# Power_Controller_V1_0.net
KiCad netlist of a schematic drawn in Altium Designer
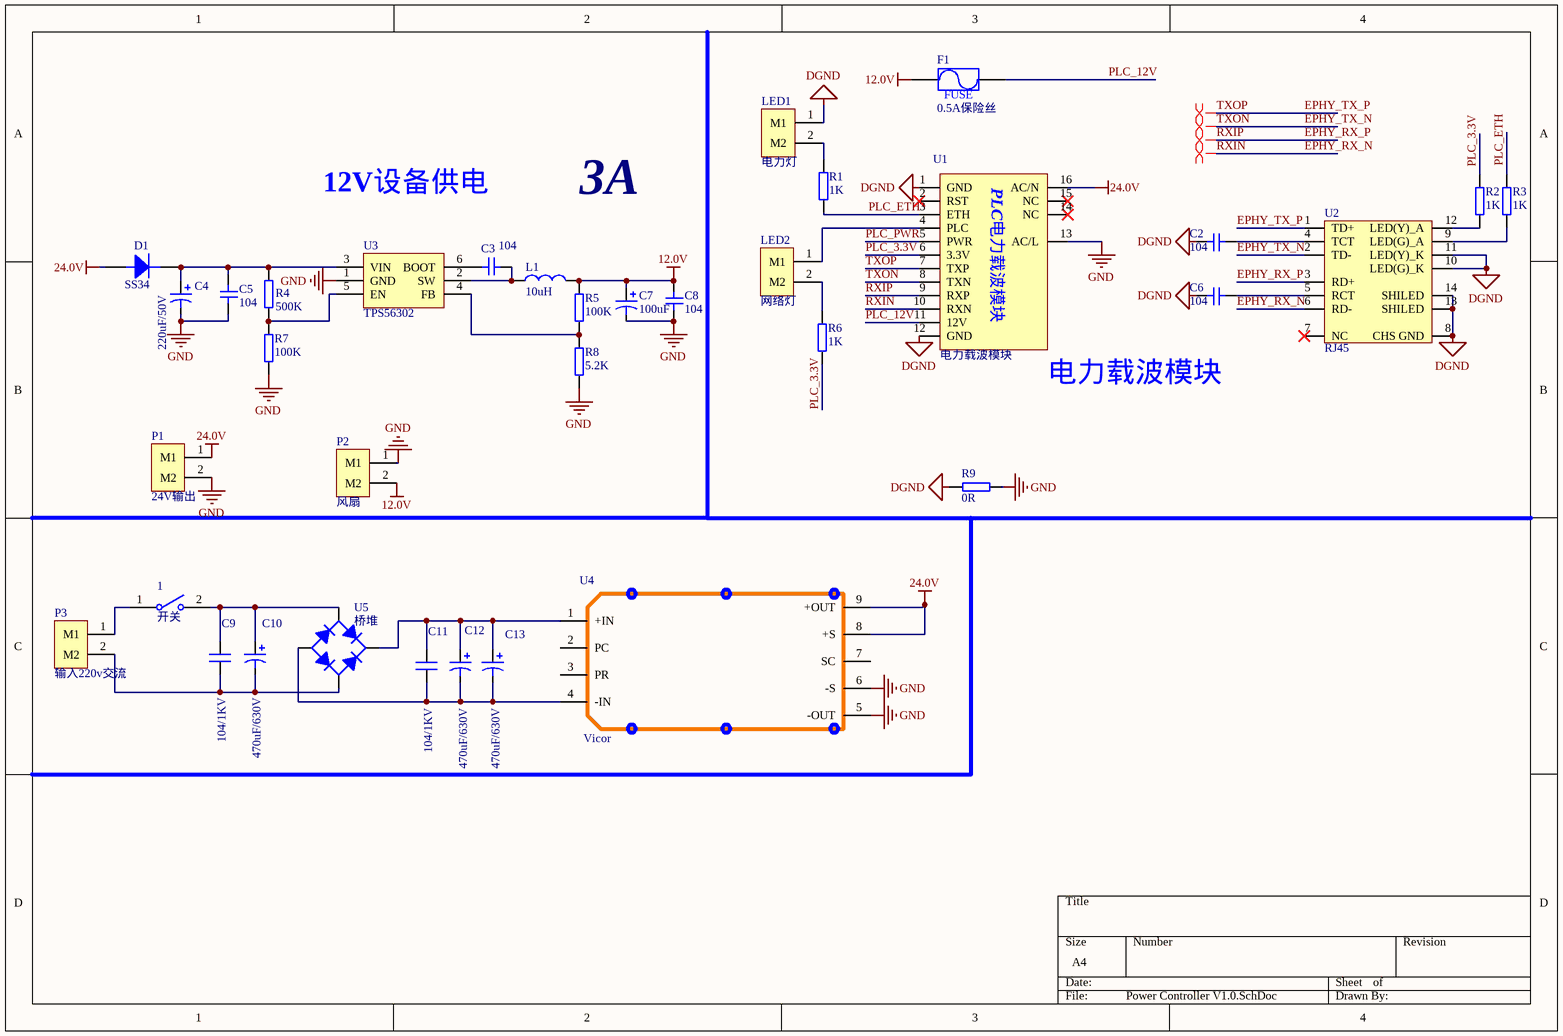
[diagram p0: Power Controller V1.0.SchDoc]

(export (version "E")
  (design (tool "Eeschema 10.0.6"))
  (components
    (comp (ref "1") (value "开关") (footprint "XT60-F") (libsource (lib "Schlib2") (part "开关")))
    (comp (ref "C2")
      (value "104")
      (footprint "0805C")
      (description "无极贴片电容")
      (libsource (lib "集大电协1.1.2") (part "Cap1"))
    )
    (comp (ref "C3")
      (value "104")
      (footprint "0805C")
      (description "无极贴片电容")
      (libsource (lib "集大电协1.5") (part "Cap1"))
    )
    (comp (ref "C4")
      (value "220uF/50V")
      (footprint "RB.1.2")
      (description "直插极性电容")
      (libsource (lib "集大电协1.5") (part "Cap3"))
    )
    (comp (ref "C5")
      (value "104")
      (footprint "0805C")
      (description "无极贴片电容")
      (libsource (lib "集大电协1.5") (part "Cap1"))
    )
    (comp (ref "C6")
      (value "104")
      (footprint "0805C")
      (description "无极贴片电容")
      (libsource (lib "集大电协1.1.2") (part "Cap1"))
    )
    (comp (ref "C7")
      (value "100uF")
      (footprint "TAJ-C")
      (description "极性贴片电容")
      (libsource (lib "集大电协1.5") (part "Pol Cap"))
    )
    (comp (ref "C8")
      (value "104")
      (footprint "0805C")
      (description "无极贴片电容")
      (libsource (lib "集大电协1.5") (part "Cap1"))
    )
    (comp (ref "C9")
      (value "104/1KV")
      (footprint "无极性直插电容")
      (description "无极直插电容")
      (libsource (lib "集大电协1.5(1)") (part "Cap2"))
    )
    (comp (ref "C10")
      (value "470uF/630V")
      (footprint "RB.2.4")
      (description "直插极性电容")
      (libsource (lib "集大电协1.5(1)") (part "Cap3"))
    )
    (comp (ref "C11")
      (value "104/1KV")
      (footprint "无极性直插电容")
      (description "无极直插电容")
      (libsource (lib "集大电协1.5(1)") (part "Cap2"))
    )
    (comp (ref "C12")
      (value "470uF/630V")
      (footprint "RB.2.4")
      (description "直插极性电容")
      (libsource (lib "集大电协1.5(1)") (part "Cap3"))
    )
    (comp (ref "C13")
      (value "470uF/630V")
      (footprint "RB.2.4")
      (description "直插极性电容")
      (libsource (lib "集大电协1.5(1)") (part "Cap3"))
    )
    (comp (ref "D1")
      (value "SS34")
      (footprint "SMA/DO-214AC")
      (description "二极管")
      (libsource (lib "集大电协1.5") (part "Diode"))
    )
    (comp (ref "F1")
      (value "0.5A保险丝")
      (footprint "FUSE-1206")
      (description "保险丝")
      (libsource (lib "集大电协1.2") (part "Fuse"))
    )
    (comp (ref "L1")
      (value "10uH")
      (footprint "CDRH124")
      (description "电感")
      (libsource (lib "集大电协1.5") (part "L"))
    )
    (comp (ref "LED1")
      (value "电力灯")
      (footprint "XH2/2.54mm/180")
      (description "2PIN")
      (libsource (lib "集大电协1.5") (part "接线端子-2PIN"))
    )
    (comp (ref "LED2")
      (value "网络灯")
      (footprint "XH2/2.54mm/180")
      (description "2PIN")
      (libsource (lib "集大电协1.5") (part "接线端子-2PIN"))
    )
    (comp (ref "P1")
      (value "24V输出")
      (footprint "XT60-F")
      (description "2PIN")
      (libsource (lib "集大电协1.5(1)") (part "接线端子-2PIN"))
    )
    (comp (ref "P2")
      (value "风扇")
      (footprint "接线端子(2.54mm)-2PIN")
      (description "2PIN")
      (libsource (lib "集大电协1.5(1)") (part "接线端子-2PIN"))
    )
    (comp (ref "P3")
      (value "输入220v交流")
      (footprint "XT60-F")
      (description "2PIN")
      (libsource (lib "集大电协1.5(1)") (part "接线端子-2PIN"))
    )
    (comp (ref "R1")
      (value "1K")
      (footprint "0805R")
      (description "电阻")
      (libsource (lib "集大电协1.5(1)") (part "Res"))
    )
    (comp (ref "R2")
      (value "1K")
      (footprint "0805R")
      (description "电阻")
      (libsource (lib "集大电协1.2") (part "Res"))
    )
    (comp (ref "R3")
      (value "1K")
      (footprint "0805R")
      (description "电阻")
      (libsource (lib "集大电协1.2") (part "Res"))
    )
    (comp (ref "R4")
      (value "500K")
      (footprint "0805R")
      (description "电阻")
      (libsource (lib "集大电协1.5") (part "Res"))
    )
    (comp (ref "R5")
      (value "100K")
      (footprint "0805R")
      (description "电阻")
      (libsource (lib "集大电协1.5") (part "Res"))
    )
    (comp (ref "R6")
      (value "1K")
      (footprint "0805R")
      (description "电阻")
      (libsource (lib "集大电协1.5(1)") (part "Res"))
    )
    (comp (ref "R7")
      (value "100K")
      (footprint "0805R")
      (description "电阻")
      (libsource (lib "集大电协1.5") (part "Res"))
    )
    (comp (ref "R8")
      (value "5.2K")
      (footprint "0805R")
      (description "电阻")
      (libsource (lib "集大电协1.5") (part "Res"))
    )
    (comp (ref "R9")
      (value "0R")
      (footprint "0805R")
      (description "电阻")
      (libsource (lib "集大电协1.5(1)") (part "Res"))
    )
    (comp (ref "U1")
      (value "电力载波模块")
      (footprint "电力载波模块6410")
      (libsource (lib "集大电协1.2") (part "电力载波模块6410"))
    )
    (comp (ref "U2") (value "RJ45") (footprint "RJ45") (libsource (lib "集大电协1.2") (part "RJ45")))
    (comp (ref "U3") (value "TPS56302") (footprint "SOT23-6") (libsource (lib "集大电协1.5") (part "TPS54302")))
    (comp (ref "U4")
      (value "Vicor")
      (footprint "vicor")
      (libsource (lib "集大电协1.5(1)") (part "滨达模块（220V--24V）"))
    )
    (comp (ref "U5") (value "桥堆") (footprint "整流全桥") (libsource (lib "集大电协1.5(1)") (part "桥堆")))
  )
  (nets
    (net (code "1") (name "/EPHY_RX_N") (class "Default")
      (node (ref "U1") (pin "10") (pinfunction "RXN_10") (pintype "passive"))
      (node (ref "U2") (pin "6") (pinfunction "RD-_6") (pintype "passive"))
    )
    (net (code "2") (name "/EPHY_RX_P") (class "Default")
      (node (ref "U1") (pin "9") (pinfunction "RXP_9") (pintype "passive"))
      (node (ref "U2") (pin "3") (pinfunction "RD+_3") (pintype "passive"))
    )
    (net (code "3") (name "/EPHY_TX_N") (class "Default")
      (node (ref "U1") (pin "8") (pinfunction "TXN_8") (pintype "passive"))
      (node (ref "U2") (pin "2") (pinfunction "TD-_2") (pintype "passive"))
    )
    (net (code "4") (name "/EPHY_TX_P") (class "Default")
      (node (ref "U1") (pin "7") (pinfunction "TXP_7") (pintype "passive"))
      (node (ref "U2") (pin "1") (pinfunction "TD+_1") (pintype "passive"))
    )
    (net (code "5") (name "/PLC_3.3V") (class "Default")
      (node (ref "R2") (pin "2") (pinfunction "2_2") (pintype "passive"))
      (node (ref "R6") (pin "1") (pinfunction "1_1") (pintype "passive"))
      (node (ref "U1") (pin "6") (pinfunction "3.3V_6") (pintype "passive"))
    )
    (net (code "6") (name "/PLC_12V") (class "Default")
      (node (ref "F1") (pin "2") (pinfunction "2_2") (pintype "passive"))
      (node (ref "U1") (pin "11") (pinfunction "12V_11") (pintype "passive"))
    )
    (net (code "7") (name "/PLC_ETH") (class "Default")
      (node (ref "R1") (pin "2") (pinfunction "2_2") (pintype "passive"))
      (node (ref "R3") (pin "1") (pinfunction "1_1") (pintype "passive"))
      (node (ref "U1") (pin "3") (pinfunction "ETH_3") (pintype "passive"))
    )
    (net (code "8") (name "/PLC_PWR") (class "Default")
      (node (ref "U1") (pin "5") (pinfunction "PWR_5") (pintype "passive"))
    )
    (net (code "9") (name "12.0V") (class "Default")
      (node (ref "C7") (pin "1") (pinfunction "1_1") (pintype "passive"))
      (node (ref "C8") (pin "2") (pinfunction "2_2") (pintype "passive"))
      (node (ref "F1") (pin "1") (pinfunction "1_1") (pintype "passive"))
      (node (ref "L1") (pin "2") (pinfunction "2_2") (pintype "passive"))
      (node (ref "P2") (pin "2") (pinfunction "M2_2") (pintype "passive"))
      (node (ref "R5") (pin "2") (pinfunction "2_2") (pintype "passive"))
    )
    (net (code "10") (name "24.0V") (class "Default")
      (node (ref "D1") (pin "1") (pintype "passive"))
      (node (ref "P1") (pin "1") (pinfunction "M1_1") (pintype "passive"))
      (node (ref "U1") (pin "16") (pinfunction "AC/N_16") (pintype "passive"))
      (node (ref "U4") (pin "8") (pinfunction "+S_8") (pintype "passive"))
      (node (ref "U4") (pin "9") (pinfunction "+OUT_9") (pintype "passive"))
    )
    (net (code "11") (name "DGND") (class "Default")
      (node (ref "C2") (pin "1") (pinfunction "1_1") (pintype "passive"))
      (node (ref "C6") (pin "1") (pinfunction "1_1") (pintype "passive"))
      (node (ref "LED1") (pin "1") (pinfunction "M1_1") (pintype "passive"))
      (node (ref "R9") (pin "2") (pinfunction "2_2") (pintype "passive"))
      (node (ref "U1") (pin "1") (pinfunction "GND_1") (pintype "passive"))
      (node (ref "U1") (pin "12") (pinfunction "GND_12") (pintype "passive"))
      (node (ref "U2") (pin "10") (pinfunction "LED(G)_K_10") (pintype "passive"))
      (node (ref "U2") (pin "11") (pinfunction "LED(Y)_K_11") (pintype "passive"))
      (node (ref "U2") (pin "13") (pinfunction "SHILED_13") (pintype "passive"))
      (node (ref "U2") (pin "14") (pinfunction "SHILED_14") (pintype "passive"))
      (node (ref "U2") (pin "8") (pinfunction "CHS_GND_8") (pintype "passive"))
    )
    (net (code "12") (name "GND") (class "Default")
      (node (ref "C4") (pin "2") (pinfunction "2_2") (pintype "passive"))
      (node (ref "C5") (pin "1") (pinfunction "1_1") (pintype "passive"))
      (node (ref "C7") (pin "2") (pinfunction "2_2") (pintype "passive"))
      (node (ref "C8") (pin "1") (pinfunction "1_1") (pintype "passive"))
      (node (ref "P1") (pin "2") (pinfunction "M2_2") (pintype "passive"))
      (node (ref "P2") (pin "1") (pinfunction "M1_1") (pintype "passive"))
      (node (ref "R7") (pin "1") (pinfunction "1_1") (pintype "passive"))
      (node (ref "R8") (pin "1") (pinfunction "1_1") (pintype "passive"))
      (node (ref "R9") (pin "1") (pinfunction "1_1") (pintype "passive"))
      (node (ref "U1") (pin "13") (pinfunction "AC/L_13") (pintype "passive"))
      (node (ref "U3") (pin "1") (pinfunction "GND_1") (pintype "passive"))
      (node (ref "U4") (pin "5") (pinfunction "-OUT_5") (pintype "passive"))
      (node (ref "U4") (pin "6") (pinfunction "-S_6") (pintype "passive"))
    )
    (net (code "13") (name "Net-(1-Pad2)") (class "Default")
      (node (ref "1") (pin "2") (pinfunction "2_2") (pintype "passive"))
      (node (ref "C10") (pin "1") (pinfunction "1_1") (pintype "passive"))
      (node (ref "C9") (pin "2") (pinfunction "2_2") (pintype "passive"))
      (node (ref "U5") (pin "AC1") (pinfunction "AC1_AC1") (pintype "passive"))
    )
    (net (code "14") (name "Net-(LED1-M2)") (class "Default")
      (node (ref "LED1") (pin "2") (pinfunction "M2_2") (pintype "passive"))
      (node (ref "R1") (pin "1") (pinfunction "1_1") (pintype "passive"))
    )
    (net (code "15") (name "Net-(LED2-M1)") (class "Default")
      (node (ref "LED2") (pin "1") (pinfunction "M1_1") (pintype "passive"))
      (node (ref "U1") (pin "4") (pinfunction "PLC_4") (pintype "passive"))
    )
    (net (code "16") (name "Net-(LED2-M2)") (class "Default")
      (node (ref "LED2") (pin "2") (pinfunction "M2_2") (pintype "passive"))
      (node (ref "R6") (pin "2") (pinfunction "2_2") (pintype "passive"))
    )
    (net (code "17") (name "Net-(P3-M1)") (class "Default")
      (node (ref "1") (pin "1") (pinfunction "1_1") (pintype "passive"))
      (node (ref "P3") (pin "1") (pinfunction "M1_1") (pintype "passive"))
    )
    (net (code "18") (name "Net-(P3-M2)") (class "Default")
      (node (ref "C10") (pin "2") (pinfunction "2_2") (pintype "passive"))
      (node (ref "C9") (pin "1") (pinfunction "1_1") (pintype "passive"))
      (node (ref "P3") (pin "2") (pinfunction "M2_2") (pintype "passive"))
      (node (ref "U5") (pin "AC2") (pinfunction "AC2_AC2") (pintype "passive"))
    )
    (net (code "19") (name "Net-(U2-LED(G)_A)") (class "Default")
      (node (ref "R3") (pin "2") (pinfunction "2_2") (pintype "passive"))
      (node (ref "U2") (pin "9") (pinfunction "LED(G)_A_9") (pintype "passive"))
    )
    (net (code "20") (name "Net-(U2-LED(Y)_A)") (class "Default")
      (node (ref "R2") (pin "1") (pinfunction "1_1") (pintype "passive"))
      (node (ref "U2") (pin "12") (pinfunction "LED(Y)_A_12") (pintype "passive"))
    )
    (net (code "21") (name "Net-(U2-RCT)") (class "Default")
      (node (ref "C6") (pin "2") (pinfunction "2_2") (pintype "passive"))
      (node (ref "U2") (pin "5") (pinfunction "RCT_5") (pintype "passive"))
    )
    (net (code "22") (name "Net-(U2-TCT)") (class "Default")
      (node (ref "C2") (pin "2") (pinfunction "2_2") (pintype "passive"))
      (node (ref "U2") (pin "4") (pinfunction "TCT_4") (pintype "passive"))
    )
    (net (code "23") (name "Net-(U3-BOOT)") (class "Default")
      (node (ref "C3") (pin "2") (pinfunction "2_2") (pintype "passive"))
      (node (ref "U3") (pin "6") (pinfunction "BOOT_6") (pintype "passive"))
    )
    (net (code "24") (name "Net-(U3-EN)") (class "Default")
      (node (ref "R4") (pin "1") (pinfunction "1_1") (pintype "passive"))
      (node (ref "R7") (pin "2") (pinfunction "2_2") (pintype "passive"))
      (node (ref "U3") (pin "5") (pinfunction "EN_5") (pintype "passive"))
    )
    (net (code "25") (name "Net-(U3-FB)") (class "Default")
      (node (ref "R5") (pin "1") (pinfunction "1_1") (pintype "passive"))
      (node (ref "R8") (pin "2") (pinfunction "2_2") (pintype "passive"))
      (node (ref "U3") (pin "4") (pinfunction "FB_4") (pintype "passive"))
    )
    (net (code "26") (name "Net-(U3-SW)") (class "Default")
      (node (ref "C3") (pin "1") (pinfunction "1_1") (pintype "passive"))
      (node (ref "L1") (pin "1") (pinfunction "1_1") (pintype "passive"))
      (node (ref "U3") (pin "2") (pinfunction "SW_2") (pintype "passive"))
    )
    (net (code "27") (name "Net-(U3-VIN)") (class "Default")
      (node (ref "C4") (pin "1") (pinfunction "1_1") (pintype "passive"))
      (node (ref "C5") (pin "2") (pinfunction "2_2") (pintype "passive"))
      (node (ref "D1") (pin "2") (pinfunction "2_2") (pintype "passive"))
      (node (ref "R4") (pin "2") (pinfunction "2_2") (pintype "passive"))
      (node (ref "U3") (pin "3") (pinfunction "VIN_3") (pintype "passive"))
    )
    (net (code "28") (name "Net-(U4-+IN)") (class "Default")
      (node (ref "C11") (pin "2") (pinfunction "2_2") (pintype "passive"))
      (node (ref "C12") (pin "1") (pinfunction "1_1") (pintype "passive"))
      (node (ref "C13") (pin "1") (pinfunction "1_1") (pintype "passive"))
      (node (ref "U4") (pin "1") (pinfunction "+IN_1") (pintype "passive"))
      (node (ref "U5") (pin "DC+") (pinfunction "DC+_DC+") (pintype "passive"))
    )
    (net (code "29") (name "Net-(U4--IN)") (class "Default")
      (node (ref "C11") (pin "1") (pinfunction "1_1") (pintype "passive"))
      (node (ref "C12") (pin "2") (pinfunction "2_2") (pintype "passive"))
      (node (ref "C13") (pin "2") (pinfunction "2_2") (pintype "passive"))
      (node (ref "U4") (pin "4") (pinfunction "-IN_4") (pintype "passive"))
      (node (ref "U5") (pin "DC-") (pinfunction "DC-_DC-") (pintype "passive"))
    )
    (net (code "30") (name "unconnected-(U1-NC-Pad14)") (class "Default")
      (node (ref "U1") (pin "14") (pinfunction "NC_14") (pintype "passive+no_connect"))
    )
    (net (code "31") (name "unconnected-(U1-NC-Pad15)") (class "Default")
      (node (ref "U1") (pin "15") (pinfunction "NC_15") (pintype "passive+no_connect"))
    )
    (net (code "32") (name "unconnected-(U1-RST-Pad2)") (class "Default")
      (node (ref "U1") (pin "2") (pinfunction "RST_2") (pintype "passive+no_connect"))
    )
    (net (code "33") (name "unconnected-(U2-NC-Pad7)") (class "Default")
      (node (ref "U2") (pin "7") (pinfunction "NC_7") (pintype "passive+no_connect"))
    )
    (net (code "34") (name "unconnected-(U4-PC-Pad2)") (class "Default")
      (node (ref "U4") (pin "2") (pinfunction "PC_2") (pintype "passive"))
    )
    (net (code "35") (name "unconnected-(U4-PR-Pad3)") (class "Default")
      (node (ref "U4") (pin "3") (pinfunction "PR_3") (pintype "passive"))
    )
    (net (code "36") (name "unconnected-(U4-SC-Pad7)") (class "Default")
      (node (ref "U4") (pin "7") (pinfunction "SC_7") (pintype "passive"))
    )
  )
)
